# daughter.net
KiCad netlist of a schematic drawn in EAGLE
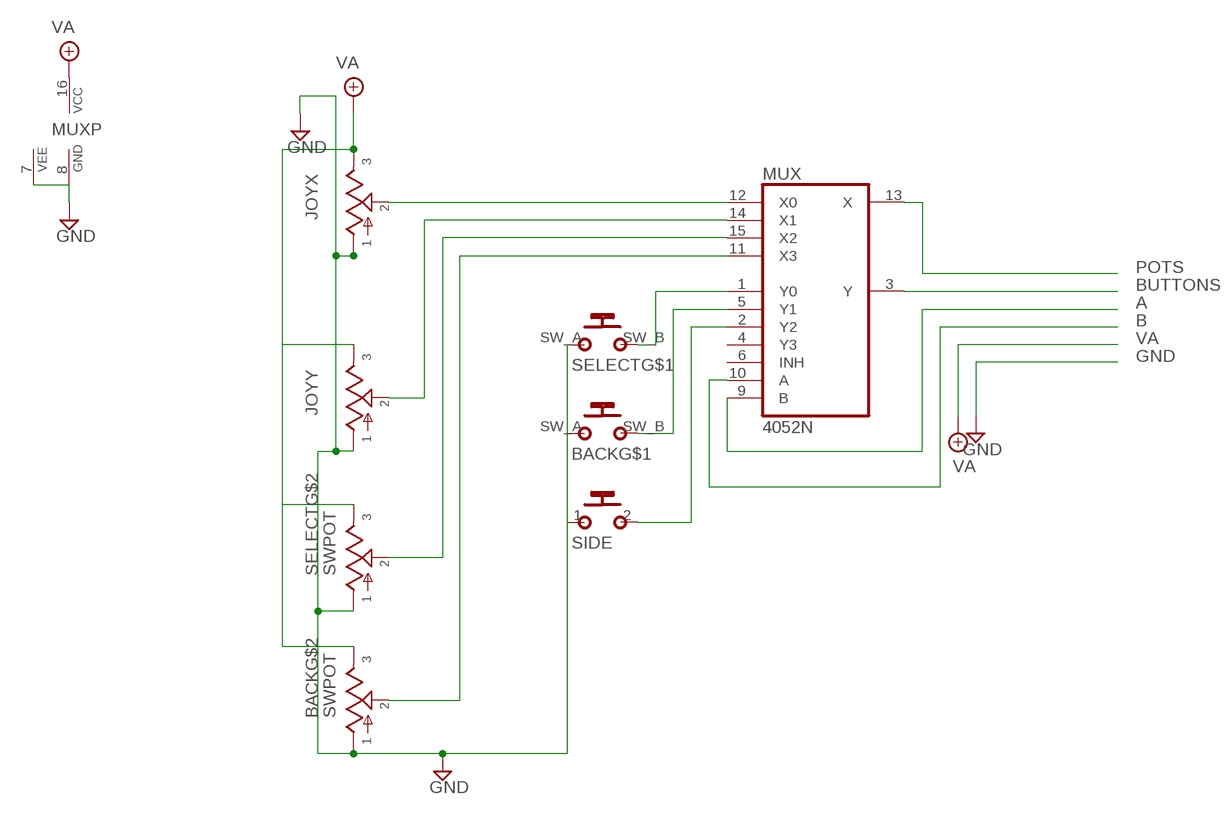
[diagram p0: schematic, sheet 1]

(export (version "E")
  (design (tool "Eeschema 10.0.6"))
  (components
    (comp (ref "BACK")
      (value "SWPOT")
      (footprint "eagle-import:SWPOT")
      (libsource (lib "eagle-import") (part "SWPOT"))
    )
    (comp (ref "JOYX")
      (value "POT")
      (footprint "eagle-import:POT")
      (libsource (lib "eagle-import") (part "POT"))
    )
    (comp (ref "JOYY")
      (value "POT")
      (footprint "eagle-import:POT")
      (libsource (lib "eagle-import") (part "POT"))
    )
    (comp (ref "MUX")
      (value "4052N")
      (footprint "eagle-import:DIL16")
      (libsource (lib "eagle-import") (part "4052N"))
    )
    (comp (ref "SELECT")
      (value "SWPOT")
      (footprint "eagle-import:SWPOT")
      (libsource (lib "eagle-import") (part "SWPOT"))
    )
    (comp (ref "SIDE")
      (value "MOMENTARY")
      (footprint "eagle-import:SPST")
      (libsource (lib "eagle-import") (part "MOMENTARY"))
    )
  )
  (nets
    (net (code "1") (name "/A") (class "Default")
      (node (ref "MUX") (pin "9") (pinfunction "B_9") (pintype "input"))
    )
    (net (code "2") (name "/B") (class "Default")
      (node (ref "MUX") (pin "10") (pinfunction "A_10") (pintype "input"))
    )
    (net (code "3") (name "/BUTTONS") (class "Default")
      (node (ref "MUX") (pin "3") (pinfunction "Y_3") (pintype "bidirectional"))
    )
    (net (code "4") (name "/POTS") (class "Default")
      (node (ref "MUX") (pin "13") (pinfunction "X_13") (pintype "bidirectional"))
    )
    (net (code "5") (name "GND") (class "Default")
      (node (ref "BACK") (pin "POT_B") (pinfunction "POT_B_POT_B") (pintype "passive"))
      (node (ref "BACK") (pin "SW_A") (pinfunction "B_A_SW_A") (pintype "passive"))
      (node (ref "JOYX") (pin "1") (pinfunction "1_1") (pintype "passive"))
      (node (ref "JOYY") (pin "1") (pinfunction "1_1") (pintype "passive"))
      (node (ref "MUX") (pin "7") (pinfunction "VEE_7") (pintype "power_in"))
      (node (ref "MUX") (pin "8") (pinfunction "GND_8") (pintype "power_in"))
      (node (ref "SELECT") (pin "POT_B") (pinfunction "POT_B_POT_B") (pintype "passive"))
      (node (ref "SELECT") (pin "SW_A") (pinfunction "B_A_SW_A") (pintype "passive"))
      (node (ref "SIDE") (pin "1") (pinfunction "P_1") (pintype "passive"))
    )
    (net (code "6") (name "Net-(BACKA-B_B)") (class "Default")
      (node (ref "BACK") (pin "SW_B") (pinfunction "B_B_SW_B") (pintype "passive"))
      (node (ref "MUX") (pin "5") (pinfunction "Y1_5") (pintype "bidirectional"))
    )
    (net (code "7") (name "Net-(MUXA-X0)") (class "Default")
      (node (ref "JOYX") (pin "2") (pinfunction "2_2") (pintype "passive"))
      (node (ref "MUX") (pin "12") (pinfunction "X0_12") (pintype "bidirectional"))
    )
    (net (code "8") (name "Net-(MUXA-X1)") (class "Default")
      (node (ref "JOYY") (pin "2") (pinfunction "2_2") (pintype "passive"))
      (node (ref "MUX") (pin "14") (pinfunction "X1_14") (pintype "bidirectional"))
    )
    (net (code "9") (name "Net-(MUXA-X2)") (class "Default")
      (node (ref "MUX") (pin "15") (pinfunction "X2_15") (pintype "bidirectional"))
      (node (ref "SELECT") (pin "POT_W") (pinfunction "POT_W_POT_W") (pintype "passive"))
    )
    (net (code "10") (name "Net-(MUXA-X3)") (class "Default")
      (node (ref "BACK") (pin "POT_W") (pinfunction "POT_W_POT_W") (pintype "passive"))
      (node (ref "MUX") (pin "11") (pinfunction "X3_11") (pintype "bidirectional"))
    )
    (net (code "11") (name "Net-(MUXA-Y0)") (class "Default")
      (node (ref "MUX") (pin "1") (pinfunction "Y0_1") (pintype "bidirectional"))
      (node (ref "SELECT") (pin "SW_B") (pinfunction "B_B_SW_B") (pintype "passive"))
    )
    (net (code "12") (name "Net-(MUXA-Y2)") (class "Default")
      (node (ref "MUX") (pin "2") (pinfunction "Y2_2") (pintype "bidirectional"))
      (node (ref "SIDE") (pin "2") (pinfunction "S_2") (pintype "passive"))
    )
    (net (code "13") (name "VA") (class "Default")
      (node (ref "BACK") (pin "POT_A") (pinfunction "POT_A_POT_A") (pintype "passive"))
      (node (ref "JOYX") (pin "3") (pinfunction "3_3") (pintype "passive"))
      (node (ref "JOYY") (pin "3") (pinfunction "3_3") (pintype "passive"))
      (node (ref "MUX") (pin "16") (pinfunction "VCC_16") (pintype "power_in"))
      (node (ref "SELECT") (pin "POT_A") (pinfunction "POT_A_POT_A") (pintype "passive"))
    )
    (net (code "14") (name "unconnected-(MUXA-INH-Pad6)") (class "Default")
      (node (ref "MUX") (pin "6") (pinfunction "INH_6") (pintype "input"))
    )
    (net (code "15") (name "unconnected-(MUXA-Y3-Pad4)") (class "Default")
      (node (ref "MUX") (pin "4") (pinfunction "Y3_4") (pintype "bidirectional"))
    )
  )
)
